# Logic.net
KiCad netlist of a schematic drawn in EAGLE
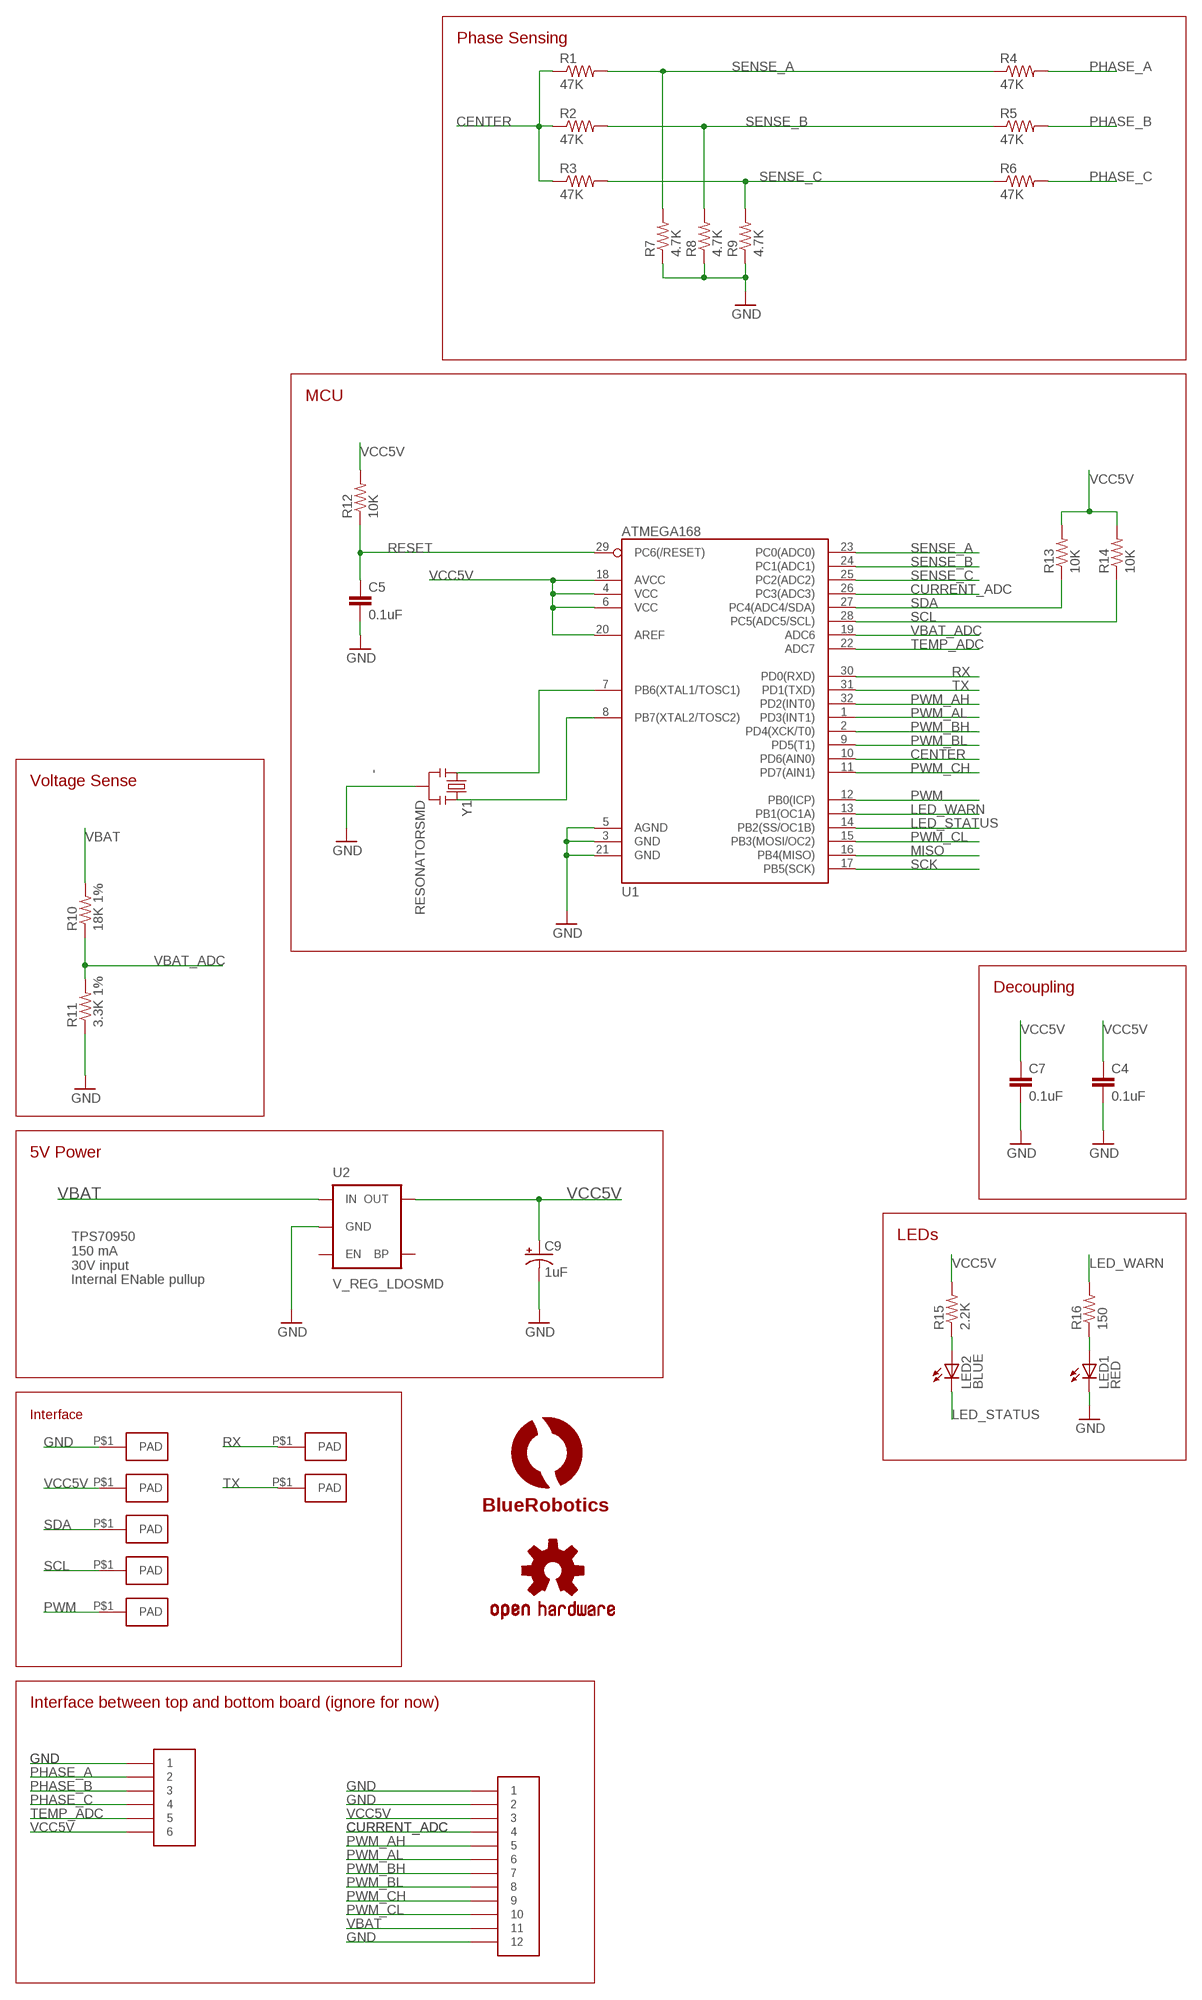
[diagram p0: schematic, sheet 1]

(export (version "E")
  (design (tool "Eeschema 10.0.6"))
  (components
    (comp (ref "C4")
      (value "0.1uF")
      (footprint "eagle-import:0603-CAP")
      (libsource (lib "eagle-import") (part "CAP0603-CAP"))
    )
    (comp (ref "C5")
      (value "0.1uF")
      (footprint "eagle-import:0603-CAP")
      (libsource (lib "eagle-import") (part "CAP0603-CAP"))
    )
    (comp (ref "C7")
      (value "0.1uF")
      (footprint "eagle-import:0603-CAP")
      (libsource (lib "eagle-import") (part "CAP0603-CAP"))
    )
    (comp (ref "C9")
      (value "1uF")
      (footprint "eagle-import:EIA3216")
      (libsource (lib "eagle-import") (part "CAP_POL1206"))
    )
    (comp (ref "LED1")
      (value "RED")
      (footprint "eagle-import:LED3MM-NS")
      (libsource (lib "eagle-import") (part "LED-3MM-NO_SILK"))
    )
    (comp (ref "LED2")
      (value "BLUE")
      (footprint "eagle-import:LED3MM-NS")
      (libsource (lib "eagle-import") (part "LED-3MM-NO_SILK"))
    )
    (comp (ref "LOGO1")
      (value "OSHW-LOGOS")
      (footprint "eagle-import:OSHW-LOGO-S")
      (libsource (lib "eagle-import") (part "OSHW-LOGOS"))
    )
    (comp (ref "R1")
      (value "47K")
      (footprint "eagle-import:0603-RES")
      (libsource (lib "eagle-import") (part "33KOHM1/10W1%(0603)"))
    )
    (comp (ref "R2")
      (value "47K")
      (footprint "eagle-import:0603-RES")
      (libsource (lib "eagle-import") (part "33KOHM1/10W1%(0603)"))
    )
    (comp (ref "R3")
      (value "47K")
      (footprint "eagle-import:0603-RES")
      (libsource (lib "eagle-import") (part "33KOHM1/10W1%(0603)"))
    )
    (comp (ref "R4")
      (value "47K")
      (footprint "eagle-import:0603-RES")
      (libsource (lib "eagle-import") (part "33KOHM1/10W1%(0603)"))
    )
    (comp (ref "R5")
      (value "47K")
      (footprint "eagle-import:0603-RES")
      (libsource (lib "eagle-import") (part "33KOHM1/10W1%(0603)"))
    )
    (comp (ref "R6")
      (value "47K")
      (footprint "eagle-import:0603-RES")
      (libsource (lib "eagle-import") (part "33KOHM1/10W1%(0603)"))
    )
    (comp (ref "R7")
      (value "4.7K")
      (footprint "eagle-import:0603-RES")
      (libsource (lib "eagle-import") (part "RESISTOR0603"))
    )
    (comp (ref "R8")
      (value "4.7K")
      (footprint "eagle-import:0603-RES")
      (libsource (lib "eagle-import") (part "RESISTOR0603"))
    )
    (comp (ref "R9")
      (value "4.7K")
      (footprint "eagle-import:0603-RES")
      (libsource (lib "eagle-import") (part "RESISTOR0603"))
    )
    (comp (ref "R10")
      (value "18K 1%")
      (footprint "eagle-import:0603-RES")
      (libsource (lib "eagle-import") (part "33KOHM1/10W1%(0603)"))
    )
    (comp (ref "R11")
      (value "3.3K 1%")
      (footprint "eagle-import:0603-RES")
      (libsource (lib "eagle-import") (part "33KOHM1/10W1%(0603)"))
    )
    (comp (ref "R12")
      (value "10K")
      (footprint "eagle-import:0603-RES")
      (libsource (lib "eagle-import") (part "33KOHM1/10W1%(0603)"))
    )
    (comp (ref "R13")
      (value "10K")
      (footprint "eagle-import:0603-RES")
      (libsource (lib "eagle-import") (part "33KOHM1/10W1%(0603)"))
    )
    (comp (ref "R14")
      (value "10K")
      (footprint "eagle-import:0603-RES")
      (libsource (lib "eagle-import") (part "33KOHM1/10W1%(0603)"))
    )
    (comp (ref "R15")
      (value "2.2K")
      (footprint "eagle-import:0603-RES")
      (libsource (lib "eagle-import") (part "RESISTOR0603-RES"))
    )
    (comp (ref "R16")
      (value "150")
      (footprint "eagle-import:0603-RES")
      (libsource (lib "eagle-import") (part "RESISTOR0603-RES"))
    )
    (comp (ref "U$3")
      (value "PAD1.5X3MM")
      (footprint "eagle-import:PAD-1.5X3MM")
      (libsource (lib "eagle-import") (part "PAD1.5X3MM"))
    )
    (comp (ref "U$4")
      (value "LOGOBR-LOGO-M")
      (footprint "eagle-import:BR-LOGO-MEDIUM")
      (libsource (lib "eagle-import") (part "LOGOBR-LOGO-M"))
    )
    (comp (ref "U$8")
      (value "PAD1.5X3MM")
      (footprint "eagle-import:PAD-1.5X3MM")
      (libsource (lib "eagle-import") (part "PAD1.5X3MM"))
    )
    (comp (ref "U$9")
      (value "PAD1.5X3MM")
      (footprint "eagle-import:PAD-1.5X3MM")
      (libsource (lib "eagle-import") (part "PAD1.5X3MM"))
    )
    (comp (ref "U$10")
      (value "PAD1.5X3MM")
      (footprint "eagle-import:PAD-1.5X3MM")
      (libsource (lib "eagle-import") (part "PAD1.5X3MM"))
    )
    (comp (ref "U$11")
      (value "PAD1.5X3MM")
      (footprint "eagle-import:PAD-1.5X3MM")
      (libsource (lib "eagle-import") (part "PAD1.5X3MM"))
    )
    (comp (ref "U$12")
      (value "PAD1.5X3MM")
      (footprint "eagle-import:PAD-1.5X3MM")
      (libsource (lib "eagle-import") (part "PAD1.5X3MM"))
    )
    (comp (ref "U$13")
      (value "PAD1.5X3MM")
      (footprint "eagle-import:PAD-1.5X3MM")
      (libsource (lib "eagle-import") (part "PAD1.5X3MM"))
    )
    (comp (ref "U$16")
      (value "HEADER-62MM")
      (footprint "eagle-import:HEADER-2MM-6POS")
      (libsource (lib "eagle-import") (part "HEADER-62MM"))
    )
    (comp (ref "U$17")
      (value "HEADER-122MM")
      (footprint "eagle-import:HEADER-2MM-12POS")
      (libsource (lib "eagle-import") (part "HEADER-122MM"))
    )
    (comp (ref "U1")
      (value "ATMEGA168")
      (footprint "eagle-import:TQFP32-08")
      (libsource (lib "eagle-import") (part "ATMEGA168"))
    )
    (comp (ref "U2")
      (value "V_REG_LDOSMD")
      (footprint "eagle-import:SOT23-5")
      (libsource (lib "eagle-import") (part "V_REG_LDOSMD"))
    )
    (comp (ref "Y1")
      (value "RESONATORSMD")
      (footprint "eagle-import:RESONATOR-SMD")
      (libsource (lib "eagle-import") (part "RESONATORSMD"))
    )
  )
  (nets
    (net (code "1") (name "/CENTER") (class "Default")
      (node (ref "R1") (pin "1") (pinfunction "1_1") (pintype "passive"))
      (node (ref "R2") (pin "1") (pinfunction "1_1") (pintype "passive"))
      (node (ref "R3") (pin "1") (pinfunction "1_1") (pintype "passive"))
      (node (ref "U1") (pin "10") (pinfunction "PD6(AIN0)_10") (pintype "bidirectional"))
    )
    (net (code "2") (name "/CURRENT_ADC") (class "Default")
      (node (ref "U$17") (pin "P$4") (pinfunction "4_P$4") (pintype "bidirectional"))
      (node (ref "U1") (pin "26") (pinfunction "PC3(ADC3)_26") (pintype "bidirectional"))
    )
    (net (code "3") (name "/LED_STATUS") (class "Default")
      (node (ref "LED2") (pin "K") (pinfunction "C_K") (pintype "passive"))
      (node (ref "U1") (pin "14") (pinfunction "PB2(SS/OC1B)_14") (pintype "bidirectional"))
    )
    (net (code "4") (name "/LED_WARN") (class "Default")
      (node (ref "R16") (pin "2") (pinfunction "2_2") (pintype "passive"))
      (node (ref "U1") (pin "13") (pinfunction "PB1(OC1A)_13") (pintype "bidirectional"))
    )
    (net (code "5") (name "/MISO") (class "Default")
      (node (ref "U1") (pin "16") (pinfunction "PB4(MISO)_16") (pintype "bidirectional"))
    )
    (net (code "6") (name "/PHASE_A") (class "Default")
      (node (ref "R4") (pin "2") (pinfunction "2_2") (pintype "passive"))
      (node (ref "U$16") (pin "P$2") (pinfunction "2_P$2") (pintype "bidirectional"))
    )
    (net (code "7") (name "/PHASE_B") (class "Default")
      (node (ref "R5") (pin "2") (pinfunction "2_2") (pintype "passive"))
      (node (ref "U$16") (pin "P$3") (pinfunction "3_P$3") (pintype "bidirectional"))
    )
    (net (code "8") (name "/PHASE_C") (class "Default")
      (node (ref "R6") (pin "2") (pinfunction "2_2") (pintype "passive"))
      (node (ref "U$16") (pin "P$4") (pinfunction "4_P$4") (pintype "bidirectional"))
    )
    (net (code "9") (name "/PWM") (class "Default")
      (node (ref "U$11") (pin "P$1") (pinfunction "PAD_P$1") (pintype "bidirectional"))
      (node (ref "U1") (pin "12") (pinfunction "PB0(ICP)_12") (pintype "bidirectional"))
    )
    (net (code "10") (name "/PWM_AH") (class "Default")
      (node (ref "U$17") (pin "P$5") (pinfunction "5_P$5") (pintype "bidirectional"))
      (node (ref "U1") (pin "32") (pinfunction "PD2(INT0)_32") (pintype "bidirectional"))
    )
    (net (code "11") (name "/PWM_AL") (class "Default")
      (node (ref "U$17") (pin "P$6") (pinfunction "6_P$6") (pintype "bidirectional"))
      (node (ref "U1") (pin "1") (pinfunction "PD3(INT1)_1") (pintype "bidirectional"))
    )
    (net (code "12") (name "/PWM_BH") (class "Default")
      (node (ref "U$17") (pin "P$7") (pinfunction "7_P$7") (pintype "bidirectional"))
      (node (ref "U1") (pin "2") (pinfunction "PD4(XCK/T0)_2") (pintype "bidirectional"))
    )
    (net (code "13") (name "/PWM_BL") (class "Default")
      (node (ref "U$17") (pin "P$8") (pinfunction "8_P$8") (pintype "bidirectional"))
      (node (ref "U1") (pin "9") (pinfunction "PD5(T1)_9") (pintype "bidirectional"))
    )
    (net (code "14") (name "/PWM_CH") (class "Default")
      (node (ref "U$17") (pin "P$9") (pinfunction "9_P$9") (pintype "bidirectional"))
      (node (ref "U1") (pin "11") (pinfunction "PD7(AIN1)_11") (pintype "bidirectional"))
    )
    (net (code "15") (name "/PWM_CL") (class "Default")
      (node (ref "U$17") (pin "P$10") (pinfunction "10_P$10") (pintype "bidirectional"))
      (node (ref "U1") (pin "15") (pinfunction "PB3(MOSI/OC2)_15") (pintype "bidirectional"))
    )
    (net (code "16") (name "/RESET") (class "Default")
      (node (ref "C5") (pin "1") (pinfunction "1_1") (pintype "passive"))
      (node (ref "R12") (pin "1") (pinfunction "1_1") (pintype "passive"))
      (node (ref "U1") (pin "29") (pinfunction "PC6(/RESET)_29") (pintype "bidirectional"))
    )
    (net (code "17") (name "/RX") (class "Default")
      (node (ref "U$12") (pin "P$1") (pinfunction "PAD_P$1") (pintype "bidirectional"))
      (node (ref "U1") (pin "30") (pinfunction "PD0(RXD)_30") (pintype "bidirectional"))
    )
    (net (code "18") (name "/SCK") (class "Default")
      (node (ref "U1") (pin "17") (pinfunction "PB5(SCK)_17") (pintype "bidirectional"))
    )
    (net (code "19") (name "/SCL") (class "Default")
      (node (ref "R14") (pin "1") (pinfunction "1_1") (pintype "passive"))
      (node (ref "U$10") (pin "P$1") (pinfunction "PAD_P$1") (pintype "bidirectional"))
      (node (ref "U1") (pin "28") (pinfunction "PC5(ADC5/SCL)_28") (pintype "bidirectional"))
    )
    (net (code "20") (name "/SDA") (class "Default")
      (node (ref "R13") (pin "1") (pinfunction "1_1") (pintype "passive"))
      (node (ref "U$9") (pin "P$1") (pinfunction "PAD_P$1") (pintype "bidirectional"))
      (node (ref "U1") (pin "27") (pinfunction "PC4(ADC4/SDA)_27") (pintype "bidirectional"))
    )
    (net (code "21") (name "/SENSE_A") (class "Default")
      (node (ref "R1") (pin "2") (pinfunction "2_2") (pintype "passive"))
      (node (ref "R4") (pin "1") (pinfunction "1_1") (pintype "passive"))
      (node (ref "R7") (pin "2") (pinfunction "2_2") (pintype "passive"))
      (node (ref "U1") (pin "23") (pinfunction "PC0(ADC0)_23") (pintype "bidirectional"))
    )
    (net (code "22") (name "/SENSE_B") (class "Default")
      (node (ref "R2") (pin "2") (pinfunction "2_2") (pintype "passive"))
      (node (ref "R5") (pin "1") (pinfunction "1_1") (pintype "passive"))
      (node (ref "R8") (pin "2") (pinfunction "2_2") (pintype "passive"))
      (node (ref "U1") (pin "24") (pinfunction "PC1(ADC1)_24") (pintype "bidirectional"))
    )
    (net (code "23") (name "/SENSE_C") (class "Default")
      (node (ref "R3") (pin "2") (pinfunction "2_2") (pintype "passive"))
      (node (ref "R6") (pin "1") (pinfunction "1_1") (pintype "passive"))
      (node (ref "R9") (pin "2") (pinfunction "2_2") (pintype "passive"))
      (node (ref "U1") (pin "25") (pinfunction "PC2(ADC2)_25") (pintype "bidirectional"))
    )
    (net (code "24") (name "/TEMP_ADC") (class "Default")
      (node (ref "U$16") (pin "P$5") (pinfunction "5_P$5") (pintype "bidirectional"))
      (node (ref "U1") (pin "22") (pinfunction "ADC7_22") (pintype "bidirectional"))
    )
    (net (code "25") (name "/TX") (class "Default")
      (node (ref "U$13") (pin "P$1") (pinfunction "PAD_P$1") (pintype "bidirectional"))
      (node (ref "U1") (pin "31") (pinfunction "PD1(TXD)_31") (pintype "bidirectional"))
    )
    (net (code "26") (name "/VBAT") (class "Default")
      (node (ref "R10") (pin "2") (pinfunction "2_2") (pintype "passive"))
      (node (ref "U$17") (pin "P$11") (pinfunction "11_P$11") (pintype "bidirectional"))
      (node (ref "U2") (pin "1") (pinfunction "IN_1") (pintype "input"))
    )
    (net (code "27") (name "/VBAT_ADC") (class "Default")
      (node (ref "R10") (pin "1") (pinfunction "1_1") (pintype "passive"))
      (node (ref "R11") (pin "2") (pinfunction "2_2") (pintype "passive"))
      (node (ref "U1") (pin "19") (pinfunction "ADC6_19") (pintype "bidirectional"))
    )
    (net (code "28") (name "/VCC5V") (class "Default")
      (node (ref "C4") (pin "1") (pinfunction "1_1") (pintype "passive"))
      (node (ref "C7") (pin "1") (pinfunction "1_1") (pintype "passive"))
      (node (ref "C9") (pin "A") (pinfunction "+_A") (pintype "passive"))
      (node (ref "R12") (pin "2") (pinfunction "2_2") (pintype "passive"))
      (node (ref "R13") (pin "2") (pinfunction "2_2") (pintype "passive"))
      (node (ref "R14") (pin "2") (pinfunction "2_2") (pintype "passive"))
      (node (ref "R15") (pin "2") (pinfunction "2_2") (pintype "passive"))
      (node (ref "U$16") (pin "P$6") (pinfunction "6_P$6") (pintype "bidirectional"))
      (node (ref "U$17") (pin "P$3") (pinfunction "3_P$3") (pintype "bidirectional"))
      (node (ref "U$8") (pin "P$1") (pinfunction "PAD_P$1") (pintype "bidirectional"))
      (node (ref "U1") (pin "18") (pinfunction "AVCC_18") (pintype "bidirectional"))
      (node (ref "U1") (pin "20") (pinfunction "AREF_20") (pintype "bidirectional"))
      (node (ref "U1") (pin "4") (pinfunction "VCC_4") (pintype "bidirectional"))
      (node (ref "U1") (pin "6") (pinfunction "VCC_6") (pintype "bidirectional"))
      (node (ref "U2") (pin "5") (pinfunction "OUT_5") (pintype "passive"))
    )
    (net (code "29") (name "GND") (class "Default")
      (node (ref "C4") (pin "2") (pinfunction "2_2") (pintype "passive"))
      (node (ref "C5") (pin "2") (pinfunction "2_2") (pintype "passive"))
      (node (ref "C7") (pin "2") (pinfunction "2_2") (pintype "passive"))
      (node (ref "C9") (pin "C") (pinfunction "-_C") (pintype "passive"))
      (node (ref "LED1") (pin "K") (pinfunction "C_K") (pintype "passive"))
      (node (ref "R11") (pin "1") (pinfunction "1_1") (pintype "passive"))
      (node (ref "R7") (pin "1") (pinfunction "1_1") (pintype "passive"))
      (node (ref "R8") (pin "1") (pinfunction "1_1") (pintype "passive"))
      (node (ref "R9") (pin "1") (pinfunction "1_1") (pintype "passive"))
      (node (ref "U$16") (pin "P$1") (pinfunction "1_P$1") (pintype "bidirectional"))
      (node (ref "U$17") (pin "P$1") (pinfunction "1_P$1") (pintype "bidirectional"))
      (node (ref "U$17") (pin "P$12") (pinfunction "12_P$12") (pintype "bidirectional"))
      (node (ref "U$17") (pin "P$2") (pinfunction "2_P$2") (pintype "bidirectional"))
      (node (ref "U$3") (pin "P$1") (pinfunction "PAD_P$1") (pintype "bidirectional"))
      (node (ref "U1") (pin "21") (pinfunction "GND_21") (pintype "bidirectional"))
      (node (ref "U1") (pin "3") (pinfunction "GND_3") (pintype "bidirectional"))
      (node (ref "U1") (pin "5") (pinfunction "AGND_5") (pintype "bidirectional"))
      (node (ref "U2") (pin "2") (pinfunction "GND_2") (pintype "input"))
      (node (ref "Y1") (pin "2") (pinfunction "2_2") (pintype "passive"))
    )
    (net (code "30") (name "Net-(LED1-PadA)") (class "Default")
      (node (ref "LED1") (pin "A") (pinfunction "A_A") (pintype "passive"))
      (node (ref "R16") (pin "1") (pinfunction "1_1") (pintype "passive"))
    )
    (net (code "31") (name "Net-(LED2-PadA)") (class "Default")
      (node (ref "LED2") (pin "A") (pinfunction "A_A") (pintype "passive"))
      (node (ref "R15") (pin "1") (pinfunction "1_1") (pintype "passive"))
    )
    (net (code "32") (name "Net-(U1-PB6(XTAL1{slash}TOSC1))") (class "Default")
      (node (ref "U1") (pin "7") (pinfunction "PB6(XTAL1/TOSC1)_7") (pintype "bidirectional"))
      (node (ref "Y1") (pin "1") (pinfunction "1_1") (pintype "passive"))
    )
    (net (code "33") (name "Net-(U1-PB7(XTAL2{slash}TOSC2))") (class "Default")
      (node (ref "U1") (pin "8") (pinfunction "PB7(XTAL2/TOSC2)_8") (pintype "bidirectional"))
      (node (ref "Y1") (pin "3") (pinfunction "3_3") (pintype "passive"))
    )
    (net (code "34") (name "unconnected-(U2-BP-Pad4)") (class "Default")
      (node (ref "U2") (pin "4") (pinfunction "BP_4") (pintype "input"))
    )
    (net (code "35") (name "unconnected-(U2-EN-Pad3)") (class "Default")
      (node (ref "U2") (pin "3") (pinfunction "EN_3") (pintype "input"))
    )
  )
)
